# Pulchra_02.net
KiCad netlist of a schematic drawn in EAGLE
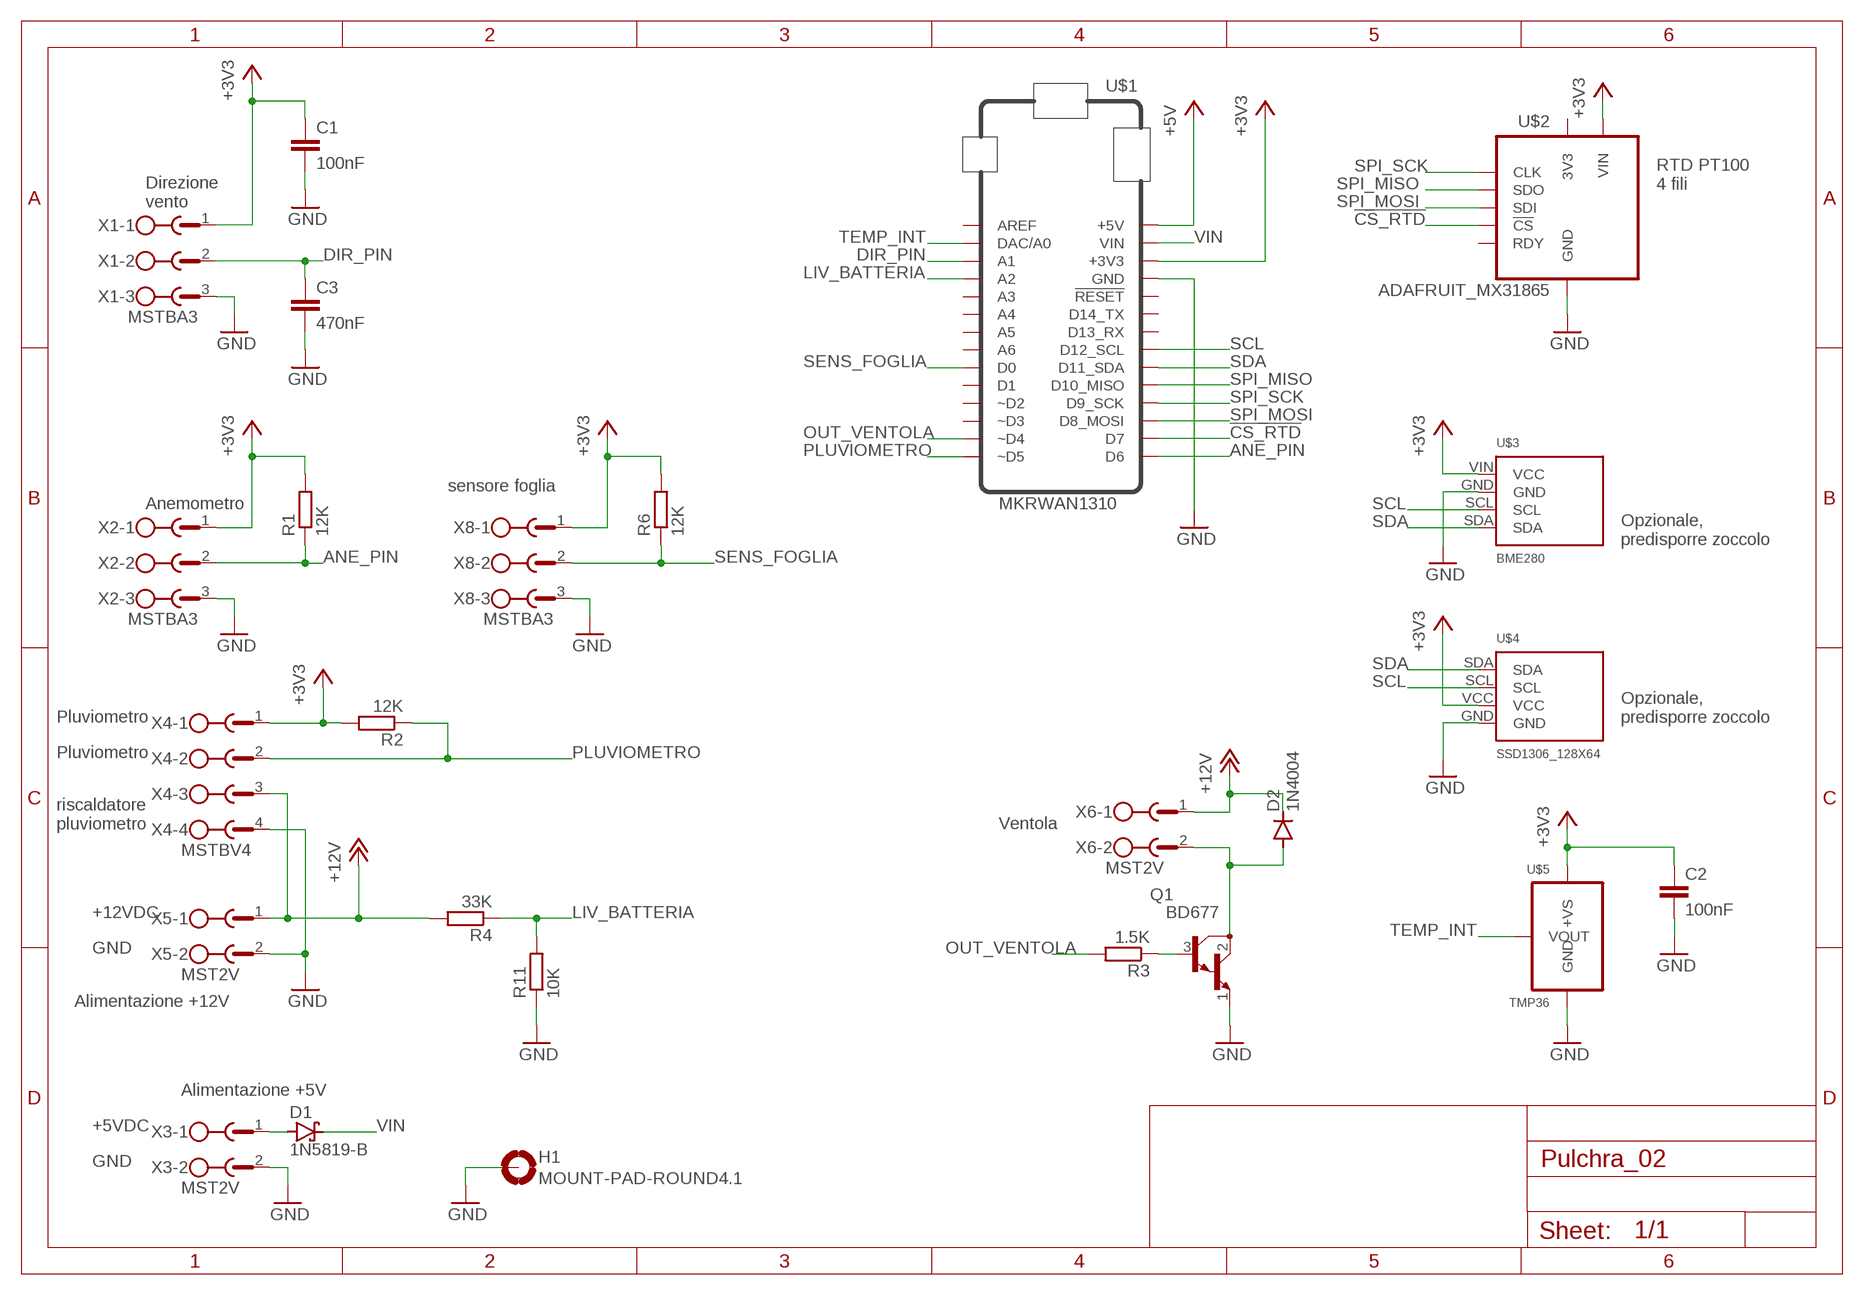
[diagram p0: schematic, sheet 1]

(export (version "E")
  (design (tool "Eeschema 10.0.6"))
  (components
    (comp (ref "C1")
      (value "100nF")
      (footprint "eagle-import:C050-025X075")
      (libsource (lib "eagle-import") (part "C-EU050-025X075"))
    )
    (comp (ref "C2")
      (value "100nF")
      (footprint "eagle-import:C050-025X075")
      (libsource (lib "eagle-import") (part "C-EU050-025X075"))
    )
    (comp (ref "C3")
      (value "470nF")
      (footprint "eagle-import:C050-025X075")
      (libsource (lib "eagle-import") (part "C-EU050-025X075"))
    )
    (comp (ref "D1")
      (value "1N5819-B")
      (footprint "eagle-import:DO41-7.6")
      (libsource (lib "eagle-import") (part "1N5819-B"))
    )
    (comp (ref "D2")
      (value "1N4004")
      (footprint "eagle-import:DO41-10")
      (libsource (lib "eagle-import") (part "1N4004"))
    )
    (comp (ref "H1")
      (value "MOUNT-PAD-ROUND4.1")
      (footprint "eagle-import:4,1-PAD")
      (libsource (lib "eagle-import") (part "MOUNT-PAD-ROUND4.1"))
    )
    (comp (ref "Q1")
      (value "BD677")
      (footprint "eagle-import:TO126")
      (libsource (lib "eagle-import") (part "BD677"))
    )
    (comp (ref "R1")
      (value "12K")
      (footprint "eagle-import:0207_10")
      (libsource (lib "eagle-import") (part "R-EU_0207/10"))
    )
    (comp (ref "R2")
      (value "12K")
      (footprint "eagle-import:0207_10")
      (libsource (lib "eagle-import") (part "R-EU_0207/10"))
    )
    (comp (ref "R3")
      (value "1.5K")
      (footprint "eagle-import:0207_10")
      (libsource (lib "eagle-import") (part "R-EU_0207/10"))
    )
    (comp (ref "R4")
      (value "33K")
      (footprint "eagle-import:0207_10")
      (libsource (lib "eagle-import") (part "R-EU_0207/10"))
    )
    (comp (ref "R6")
      (value "12K")
      (footprint "eagle-import:0207_10")
      (libsource (lib "eagle-import") (part "R-EU_0207/10"))
    )
    (comp (ref "R11")
      (value "10K")
      (footprint "eagle-import:0207_10")
      (libsource (lib "eagle-import") (part "R-EU_0207/10"))
    )
    (comp (ref "U$1")
      (value "MKRWAN1310")
      (footprint "eagle-import:MKRWAN1310")
      (libsource (lib "eagle-import") (part "MKRWAN1310"))
    )
    (comp (ref "U$2")
      (value "ADAFRUIT_MX31865")
      (footprint "eagle-import:ADAFRUIT_MAX31865")
      (libsource (lib "eagle-import") (part "ADAFRUIT_MX31865"))
    )
    (comp (ref "U$3")
      (value "BME280")
      (footprint "eagle-import:BME280_GYBMEP")
      (libsource (lib "eagle-import") (part "BME280"))
    )
    (comp (ref "U$4")
      (value "SSD1306_128X64")
      (footprint "eagle-import:128X64")
      (libsource (lib "eagle-import") (part "SSD1306_128X64"))
    )
    (comp (ref "U$5")
      (value "TMP36")
      (footprint "eagle-import:TO92")
      (libsource (lib "eagle-import") (part "TMP36"))
    )
    (comp (ref "X1")
      (value "MSTBA3")
      (footprint "eagle-import:MSTBA3")
      (fields (field (name "MF") "FARNELL") (field (name "MPN") "1757255"))
      (libsource (lib "eagle-import") (part "MSTBA3"))
    )
    (comp (ref "X2")
      (value "MSTBA3")
      (footprint "eagle-import:MSTBA3")
      (fields (field (name "MF") "FARNELL") (field (name "MPN") "1757255"))
      (libsource (lib "eagle-import") (part "MSTBA3"))
    )
    (comp (ref "X3")
      (value "MST2V")
      (footprint "eagle-import:MSTBV2")
      (libsource (lib "eagle-import") (part "MST2V"))
    )
    (comp (ref "X4")
      (value "MSTBV4")
      (footprint "eagle-import:MSTBV4")
      (fields (field (name "MPN") "MSTBV 2,5/4-GF-5.08"))
      (libsource (lib "eagle-import") (part "MSTBV4"))
    )
    (comp (ref "X5")
      (value "MST2V")
      (footprint "eagle-import:MSTBV2")
      (libsource (lib "eagle-import") (part "MST2V"))
    )
    (comp (ref "X6")
      (value "MST2V")
      (footprint "eagle-import:MSTBV2")
      (libsource (lib "eagle-import") (part "MST2V"))
    )
    (comp (ref "X8")
      (value "MSTBA3")
      (footprint "eagle-import:MSTBA3")
      (fields (field (name "MF") "FARNELL") (field (name "MPN") "1757255"))
      (libsource (lib "eagle-import") (part "MSTBA3"))
    )
  )
  (nets
    (net (code "1") (name "+3V3") (class "Default")
      (node (ref "C1") (pin "1") (pinfunction "1_1") (pintype "passive"))
      (node (ref "C2") (pin "1") (pinfunction "1_1") (pintype "passive"))
      (node (ref "R1") (pin "2") (pinfunction "2_2") (pintype "passive"))
      (node (ref "R2") (pin "2") (pinfunction "2_2") (pintype "passive"))
      (node (ref "R6") (pin "2") (pinfunction "2_2") (pintype "passive"))
      (node (ref "U$1") (pin "+3V3") (pinfunction "+3V3_+3V3") (pintype "power_in"))
      (node (ref "U$2") (pin "P1") (pinfunction "VIN_P1") (pintype "power_in"))
      (node (ref "U$3") (pin "VIN") (pinfunction "VCC_VIN") (pintype "power_in"))
      (node (ref "U$4") (pin "VCC") (pinfunction "VCC_VCC") (pintype "power_in"))
      (node (ref "U$5") (pin "1") (pinfunction "+VS_1") (pintype "power_in"))
      (node (ref "X1") (pin "1") (pinfunction "1_1") (pintype "passive"))
      (node (ref "X2") (pin "1") (pinfunction "1_1") (pintype "passive"))
      (node (ref "X4") (pin "1") (pinfunction "1_1") (pintype "passive"))
      (node (ref "X8") (pin "1") (pinfunction "1_1") (pintype "passive"))
    )
    (net (code "2") (name "+5V") (class "Default")
      (node (ref "U$1") (pin "+5V") (pinfunction "+5V_+5V") (pintype "power_in"))
    )
    (net (code "3") (name "+12V") (class "Default")
      (node (ref "D2") (pin "C") (pinfunction "C_C") (pintype "passive"))
      (node (ref "R4") (pin "2") (pinfunction "2_2") (pintype "passive"))
      (node (ref "X4") (pin "3") (pinfunction "1_3") (pintype "passive"))
      (node (ref "X5") (pin "1") (pinfunction "1_1") (pintype "passive"))
      (node (ref "X6") (pin "1") (pinfunction "1_1") (pintype "passive"))
    )
    (net (code "4") (name "/ANE_PIN") (class "Default")
      (node (ref "R1") (pin "1") (pinfunction "1_1") (pintype "passive"))
      (node (ref "U$1") (pin "D6") (pinfunction "D6_D6") (pintype "bidirectional"))
      (node (ref "X2") (pin "2") (pinfunction "1_2") (pintype "passive"))
    )
    (net (code "5") (name "/DIR_PIN") (class "Default")
      (node (ref "C3") (pin "1") (pinfunction "1_1") (pintype "passive"))
      (node (ref "U$1") (pin "A1") (pinfunction "A1_A1") (pintype "input"))
      (node (ref "X1") (pin "2") (pinfunction "1_2") (pintype "passive"))
    )
    (net (code "6") (name "/LIV_BATTERIA") (class "Default")
      (node (ref "R11") (pin "2") (pinfunction "2_2") (pintype "passive"))
      (node (ref "R4") (pin "1") (pinfunction "1_1") (pintype "passive"))
      (node (ref "U$1") (pin "A2") (pinfunction "A2_A2") (pintype "input"))
    )
    (net (code "7") (name "/OUT_VENTOLA") (class "Default")
      (node (ref "R3") (pin "2") (pinfunction "2_2") (pintype "passive"))
      (node (ref "U$1") (pin "~D4") (pinfunction "~{D4}_~D4") (pintype "bidirectional"))
    )
    (net (code "8") (name "/PLUVIOMETRO") (class "Default")
      (node (ref "R2") (pin "1") (pinfunction "1_1") (pintype "passive"))
      (node (ref "U$1") (pin "~D5") (pinfunction "~{D5}_~D5") (pintype "bidirectional"))
      (node (ref "X4") (pin "2") (pinfunction "1_2") (pintype "passive"))
    )
    (net (code "9") (name "/SCL") (class "Default")
      (node (ref "U$1") (pin "D12_SCL") (pinfunction "D12_SCL_D12_SCL") (pintype "bidirectional"))
      (node (ref "U$3") (pin "SCL") (pinfunction "SCL_SCL") (pintype "bidirectional"))
      (node (ref "U$4") (pin "SCL") (pinfunction "SCL_SCL") (pintype "bidirectional"))
    )
    (net (code "10") (name "/SDA") (class "Default")
      (node (ref "U$1") (pin "D11_SDA") (pinfunction "D11_SDA_D11_SDA") (pintype "bidirectional"))
      (node (ref "U$3") (pin "SDA") (pinfunction "SDA_SDA") (pintype "bidirectional"))
      (node (ref "U$4") (pin "SDA") (pinfunction "SDA_SDA") (pintype "bidirectional"))
    )
    (net (code "11") (name "/SENS_FOGLIA") (class "Default")
      (node (ref "R6") (pin "1") (pinfunction "1_1") (pintype "passive"))
      (node (ref "U$1") (pin "D0") (pinfunction "D0_D0") (pintype "bidirectional"))
      (node (ref "X8") (pin "2") (pinfunction "1_2") (pintype "passive"))
    )
    (net (code "12") (name "/SPI_MISO") (class "Default")
      (node (ref "U$1") (pin "D10_MISO") (pinfunction "D10_MISO_D10_MISO") (pintype "bidirectional"))
      (node (ref "U$2") (pin "P5") (pinfunction "SDO_P5") (pintype "output"))
    )
    (net (code "13") (name "/SPI_MOSI") (class "Default")
      (node (ref "U$1") (pin "D8_MOSI") (pinfunction "D8_MOSI_D8_MOSI") (pintype "bidirectional"))
      (node (ref "U$2") (pin "P6") (pinfunction "SDI_P6") (pintype "input"))
    )
    (net (code "14") (name "/SPI_SCK") (class "Default")
      (node (ref "U$1") (pin "D9_SCK") (pinfunction "D9_SCK_D9_SCK") (pintype "bidirectional"))
      (node (ref "U$2") (pin "P4") (pinfunction "CLK_P4") (pintype "input"))
    )
    (net (code "15") (name "/TEMP_INT") (class "Default")
      (node (ref "U$1") (pin "DAC0/A0") (pinfunction "DAC/A0_DAC0/A0") (pintype "input"))
      (node (ref "U$5") (pin "2") (pinfunction "VOUT_2") (pintype "output"))
    )
    (net (code "16") (name "/VIN") (class "Default")
      (node (ref "D1") (pin "C") (pinfunction "C_C") (pintype "passive"))
      (node (ref "U$1") (pin "VIN") (pinfunction "VIN_VIN") (pintype "power_in"))
    )
    (net (code "17") (name "/~{CS_RTD}") (class "Default")
      (node (ref "U$1") (pin "D7") (pinfunction "D7_D7") (pintype "bidirectional"))
      (node (ref "U$2") (pin "P7") (pinfunction "~{CS}_P7") (pintype "input"))
    )
    (net (code "18") (name "GND") (class "Default")
      (node (ref "C1") (pin "2") (pinfunction "2_2") (pintype "passive"))
      (node (ref "C2") (pin "2") (pinfunction "2_2") (pintype "passive"))
      (node (ref "C3") (pin "2") (pinfunction "2_2") (pintype "passive"))
      (node (ref "H1") (pin "B4,1") (pinfunction "MOUNT_B4,1") (pintype "passive"))
      (node (ref "Q1") (pin "1") (pinfunction "E_1") (pintype "passive"))
      (node (ref "R11") (pin "1") (pinfunction "1_1") (pintype "passive"))
      (node (ref "U$1") (pin "GND") (pinfunction "GND_GND") (pintype "power_in"))
      (node (ref "U$2") (pin "P2") (pinfunction "GND_P2") (pintype "power_in"))
      (node (ref "U$3") (pin "GND") (pinfunction "GND_GND") (pintype "power_in"))
      (node (ref "U$4") (pin "GND") (pinfunction "GND_GND") (pintype "power_in"))
      (node (ref "U$5") (pin "3") (pinfunction "GND_3") (pintype "power_in"))
      (node (ref "X1") (pin "3") (pinfunction "1_3") (pintype "passive"))
      (node (ref "X2") (pin "3") (pinfunction "1_3") (pintype "passive"))
      (node (ref "X3") (pin "2") (pinfunction "1_2") (pintype "passive"))
      (node (ref "X4") (pin "4") (pinfunction "1_4") (pintype "passive"))
      (node (ref "X5") (pin "2") (pinfunction "1_2") (pintype "passive"))
      (node (ref "X8") (pin "3") (pinfunction "1_3") (pintype "passive"))
    )
    (net (code "19") (name "Net-(D1-PadA)") (class "Default")
      (node (ref "D1") (pin "A") (pinfunction "A_A") (pintype "passive"))
      (node (ref "X3") (pin "1") (pinfunction "1_1") (pintype "passive"))
    )
    (net (code "20") (name "Net-(Q1-B)") (class "Default")
      (node (ref "Q1") (pin "3") (pinfunction "B_3") (pintype "passive"))
      (node (ref "R3") (pin "1") (pinfunction "1_1") (pintype "passive"))
    )
    (net (code "21") (name "Net-(Q1-C)") (class "Default")
      (node (ref "D2") (pin "A") (pinfunction "A_A") (pintype "passive"))
      (node (ref "Q1") (pin "2") (pinfunction "C_2") (pintype "passive"))
      (node (ref "X6") (pin "2") (pinfunction "1_2") (pintype "passive"))
    )
    (net (code "22") (name "unconnected-(U$1-PadA3)") (class "Default")
      (node (ref "U$1") (pin "A3") (pinfunction "A3_A3") (pintype "input"))
    )
    (net (code "23") (name "unconnected-(U$1-PadA4)") (class "Default")
      (node (ref "U$1") (pin "A4") (pinfunction "A4_A4") (pintype "input"))
    )
    (net (code "24") (name "unconnected-(U$1-PadA5)") (class "Default")
      (node (ref "U$1") (pin "A5") (pinfunction "A5_A5") (pintype "input"))
    )
    (net (code "25") (name "unconnected-(U$1-PadA6)") (class "Default")
      (node (ref "U$1") (pin "A6") (pinfunction "A6_A6") (pintype "input"))
    )
    (net (code "26") (name "unconnected-(U$1-PadAREF)") (class "Default")
      (node (ref "U$1") (pin "AREF") (pinfunction "AREF_AREF") (pintype "passive"))
    )
    (net (code "27") (name "unconnected-(U$1-PadD1)") (class "Default")
      (node (ref "U$1") (pin "D1") (pinfunction "D1_D1") (pintype "bidirectional"))
    )
    (net (code "28") (name "unconnected-(U$1-PadD13_RX)") (class "Default")
      (node (ref "U$1") (pin "D13_RX") (pinfunction "D13_RX_D13_RX") (pintype "bidirectional"))
    )
    (net (code "29") (name "unconnected-(U$1-PadD14_TX)") (class "Default")
      (node (ref "U$1") (pin "D14_TX") (pinfunction "D14_TX_D14_TX") (pintype "bidirectional"))
    )
    (net (code "30") (name "unconnected-(U$1-~{D2}-Pad~D2)") (class "Default")
      (node (ref "U$1") (pin "~D2") (pinfunction "~{D2}_~D2") (pintype "bidirectional"))
    )
    (net (code "31") (name "unconnected-(U$1-~{D3}-Pad~D3)") (class "Default")
      (node (ref "U$1") (pin "~D3") (pinfunction "~{D3}_~D3") (pintype "bidirectional"))
    )
    (net (code "32") (name "unconnected-(U$1-~{RESET}-Pad!RESET!)") (class "Default")
      (node (ref "U$1") (pin "!RESET!") (pinfunction "~{RESET}_!RESET!") (pintype "input"))
    )
    (net (code "33") (name "unconnected-(U$2-3V3-PadP3)") (class "Default")
      (node (ref "U$2") (pin "P3") (pinfunction "3V3_P3") (pintype "output"))
    )
    (net (code "34") (name "unconnected-(U$2-RDY-PadP8)") (class "Default")
      (node (ref "U$2") (pin "P8") (pinfunction "RDY_P8") (pintype "output"))
    )
  )
)
